# Breakout.net
KiCad netlist of a schematic drawn in EAGLE
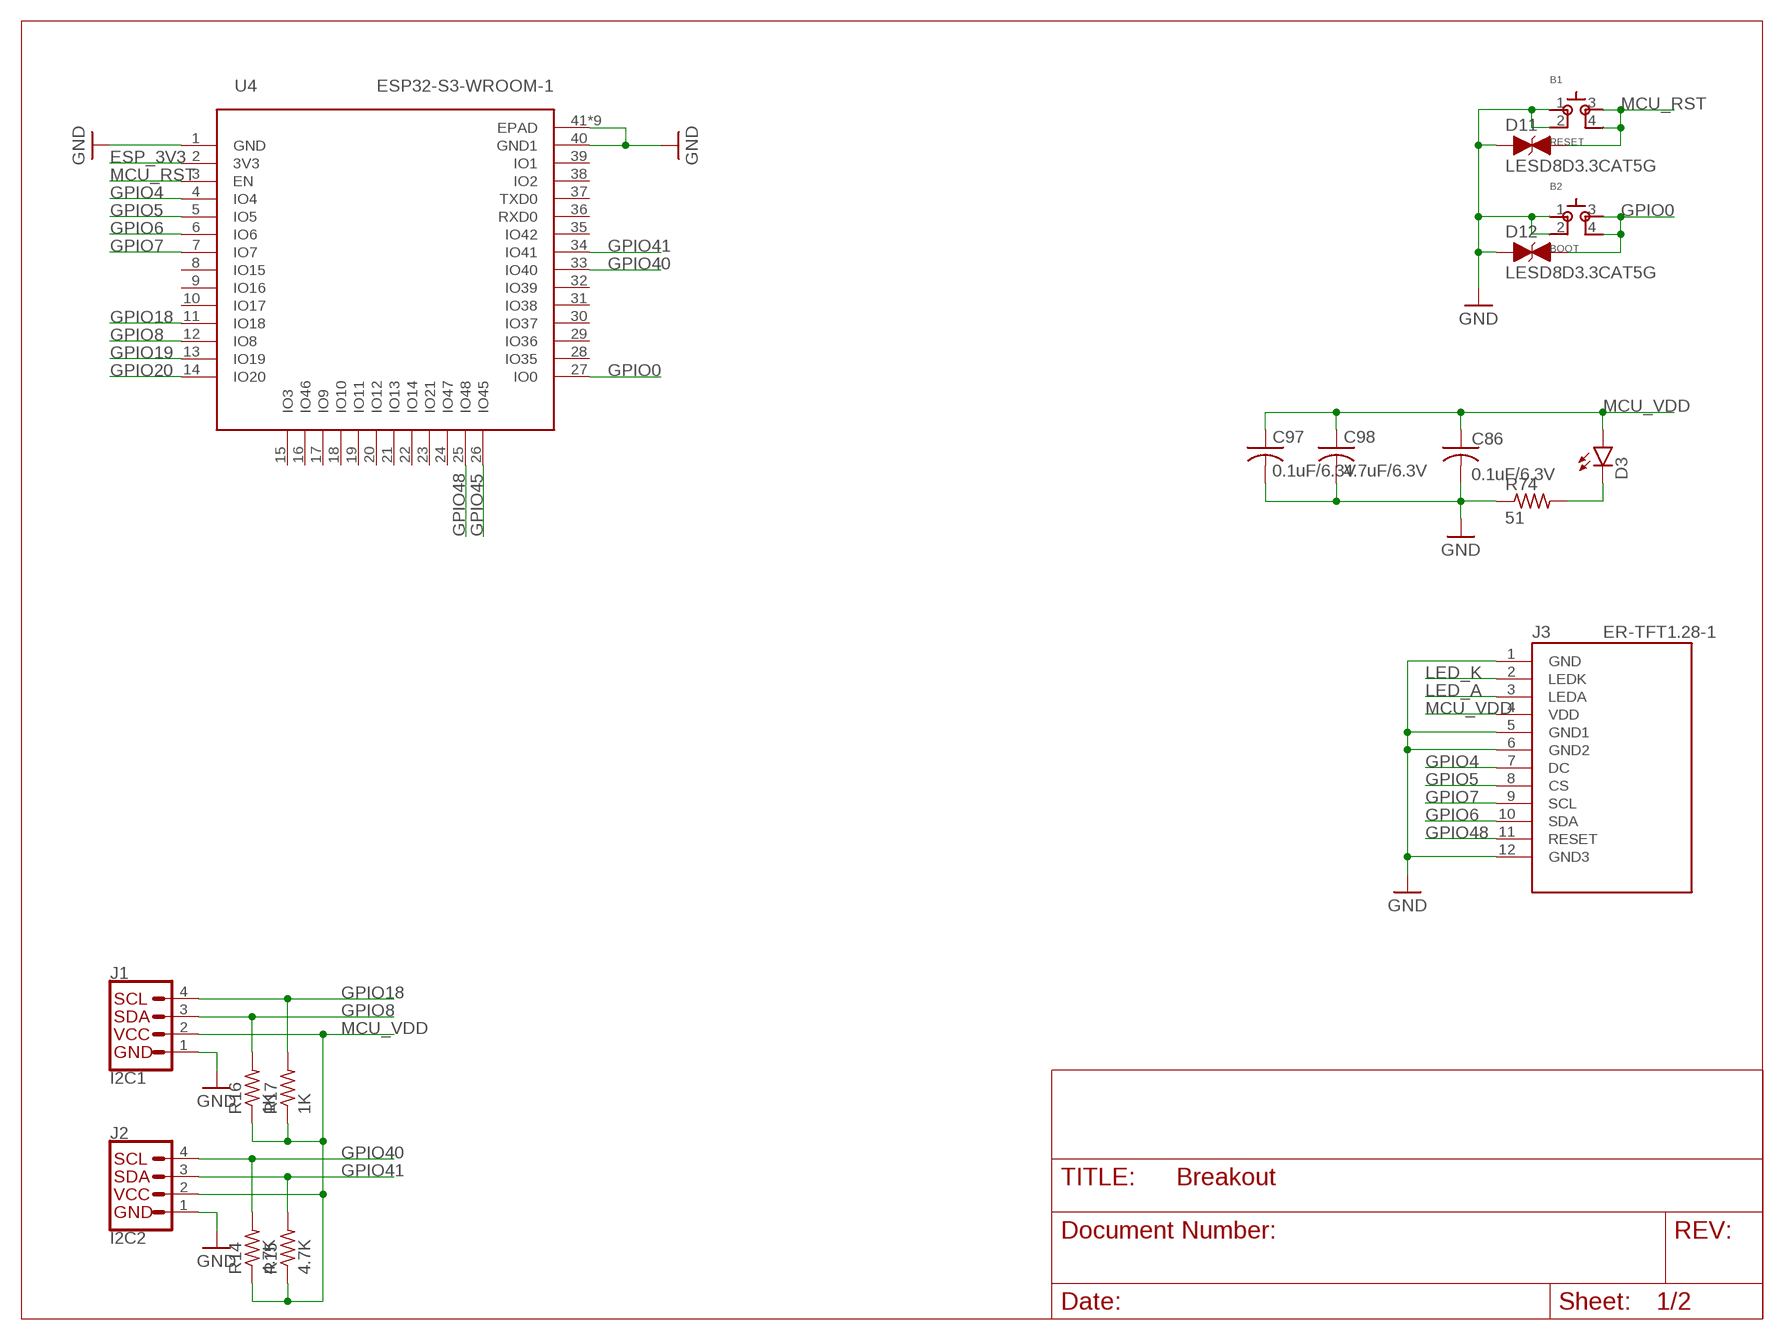
[diagram p0: schematic, sheet 1]
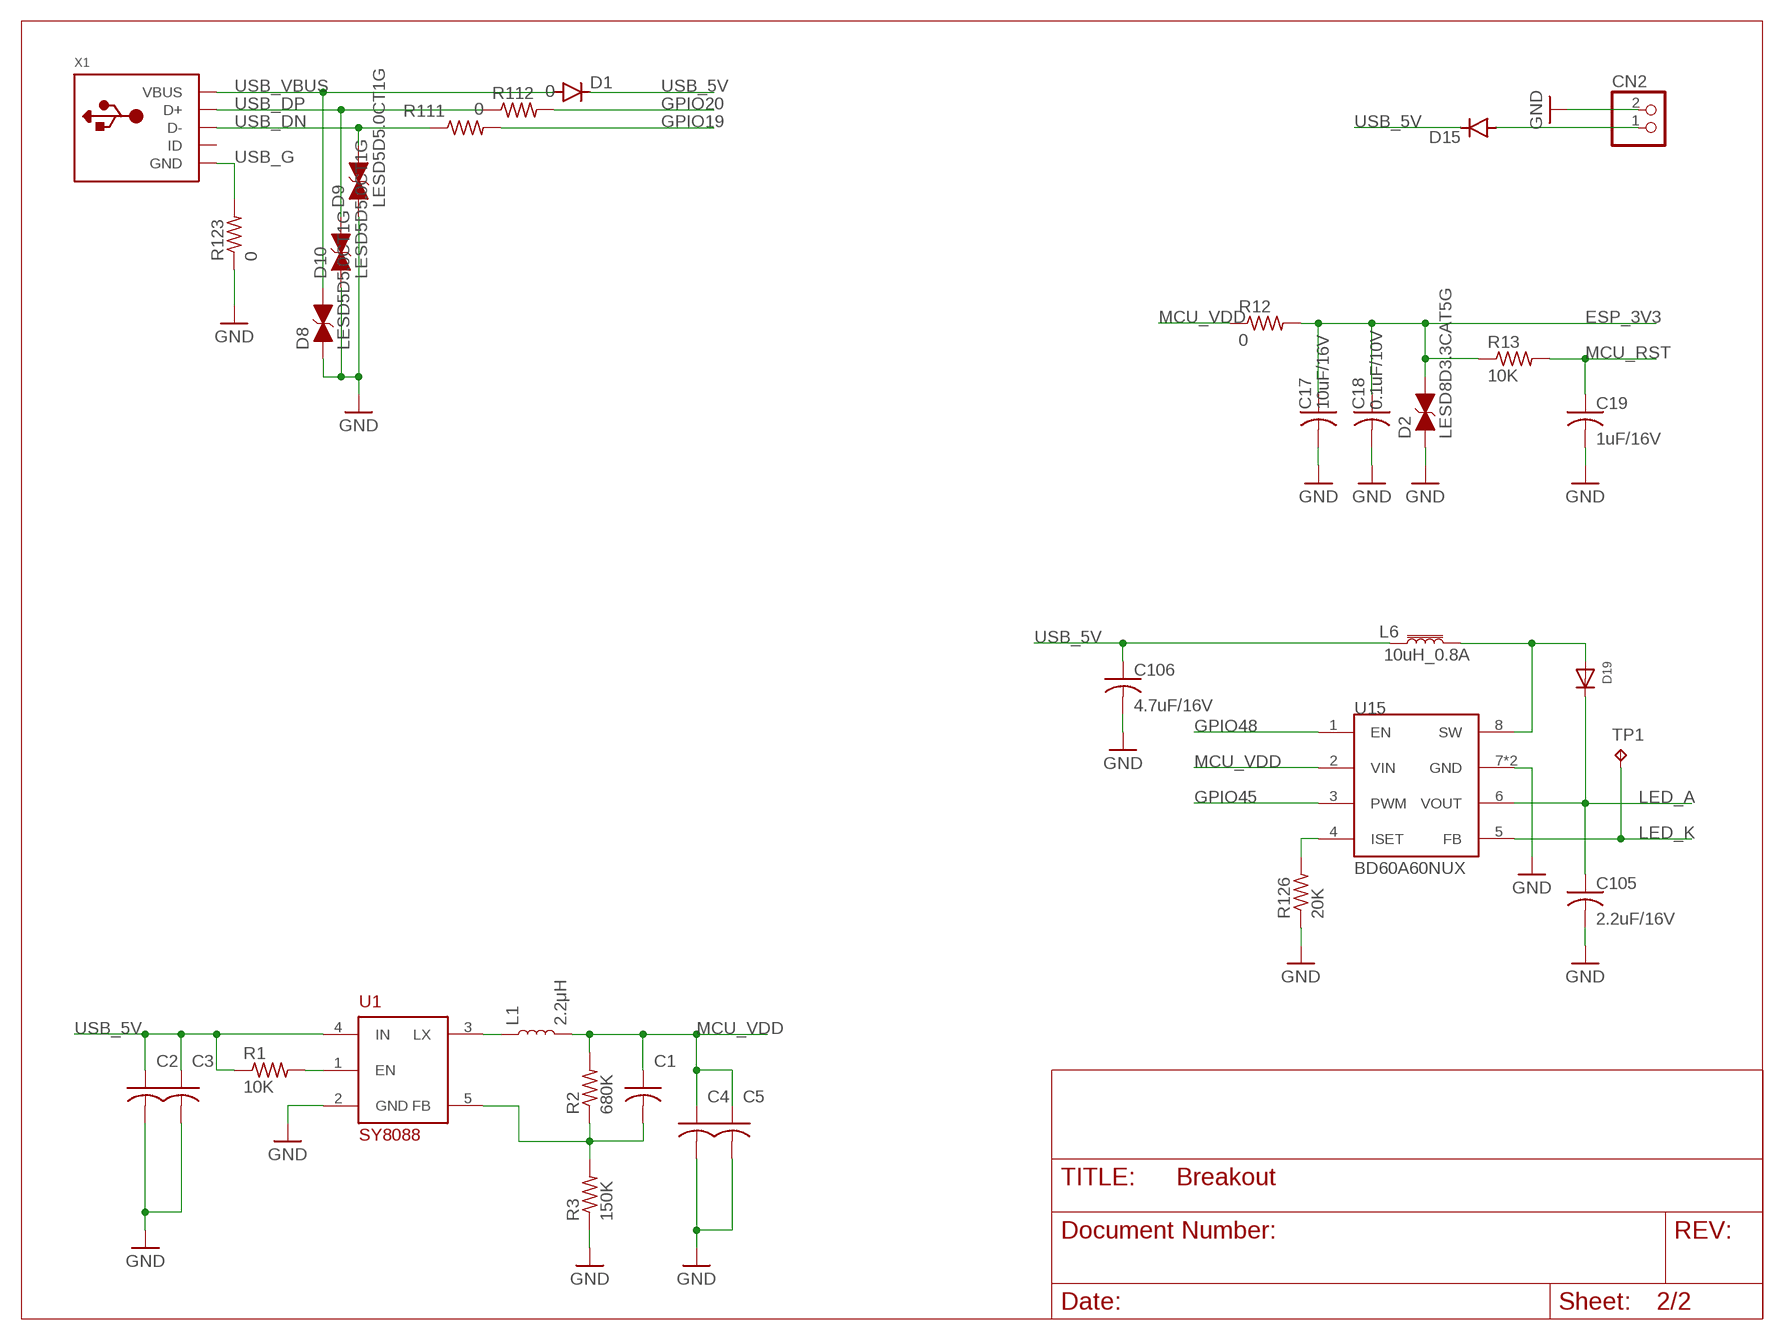
[diagram p1: schematic, sheet 2]

(export (version "E")
  (design (tool "Eeschema 10.0.6"))
  (components
    (comp (ref "B1")
      (value "RESET")
      (footprint "eagle-import:SKSCLDE010")
      (libsource (lib "eagle-import") (part "SKSCLDE010"))
    )
    (comp (ref "B2")
      (value "BOOT")
      (footprint "eagle-import:SKSCLDE010")
      (libsource (lib "eagle-import") (part "SKSCLDE010"))
    )
    (comp (ref "C86")
      (value "0.1uF/6.3V")
      (footprint "eagle-import:C0402")
      (libsource (lib "eagle-import") (part "C-USC0402"))
    )
    (comp (ref "C97")
      (value "0.1uF/6.3V")
      (footprint "eagle-import:C0402")
      (libsource (lib "eagle-import") (part "C-USC0402"))
    )
    (comp (ref "C98")
      (value "4.7uF/6.3V")
      (footprint "eagle-import:C0402")
      (libsource (lib "eagle-import") (part "C-USC0402"))
    )
    (comp (ref "D3")
      (value "LEDCHIPLED_1206")
      (footprint "eagle-import:CHIPLED_1206")
      (libsource (lib "eagle-import") (part "LEDCHIPLED_1206"))
    )
    (comp (ref "D11")
      (value "LESD8D3.3CAT5G")
      (footprint "eagle-import:SOD882")
      (libsource (lib "eagle-import") (part "LESD8D3.3CAT5G"))
    )
    (comp (ref "D12")
      (value "LESD8D3.3CAT5G")
      (footprint "eagle-import:SOD882")
      (libsource (lib "eagle-import") (part "LESD8D3.3CAT5G"))
    )
    (comp (ref "J1")
      (value "I2C1")
      (footprint "eagle-import:JST04_1MM_VERT")
      (libsource (lib "eagle-import") (part "QWIIC_CONNECTOR"))
    )
    (comp (ref "J2")
      (value "I2C2")
      (footprint "eagle-import:JST04_1MM_VERT")
      (libsource (lib "eagle-import") (part "QWIIC_CONNECTOR"))
    )
    (comp (ref "J3")
      (value "ER-TFT1.28-1")
      (footprint "eagle-import:12P-FPC")
      (libsource (lib "eagle-import") (part "ER-TFT1.28-1"))
    )
    (comp (ref "R14")
      (value "4.7K")
      (footprint "eagle-import:R0201")
      (libsource (lib "eagle-import") (part "R-US_R0201"))
    )
    (comp (ref "R15")
      (value "4.7K")
      (footprint "eagle-import:R0201")
      (libsource (lib "eagle-import") (part "R-US_R0201"))
    )
    (comp (ref "R16")
      (value "1K")
      (footprint "eagle-import:R0201")
      (libsource (lib "eagle-import") (part "R-US_R0201"))
    )
    (comp (ref "R17")
      (value "1K")
      (footprint "eagle-import:R0201")
      (libsource (lib "eagle-import") (part "R-US_R0201"))
    )
    (comp (ref "R74")
      (value "51")
      (footprint "eagle-import:R0201")
      (libsource (lib "eagle-import") (part "R-US_R0201"))
    )
    (comp (ref "U4")
      (value "ESP32-S3-WROOM-1")
      (footprint "eagle-import:QFN60_ESP32-S3-WROOM-1_EXP")
      (libsource (lib "eagle-import") (part "ESP32-S3-WROOM-1"))
    )
    (comp (ref "C1")
      (value "22pF/50V")
      (footprint "eagle-import:C0402")
      (libsource (lib "eagle-import") (part "C-USC0402"))
    )
    (comp (ref "C2")
      (value "10uF/16V")
      (footprint "eagle-import:C0603")
      (libsource (lib "eagle-import") (part "C-USC0603"))
    )
    (comp (ref "C3")
      (value "0.1uF/10V")
      (footprint "eagle-import:C0603")
      (libsource (lib "eagle-import") (part "C-USC0603"))
    )
    (comp (ref "C4")
      (value "0.1uF/10V")
      (footprint "eagle-import:C0402")
      (libsource (lib "eagle-import") (part "C-USC0402"))
    )
    (comp (ref "C5")
      (value "10uF/16V")
      (footprint "eagle-import:C0402")
      (libsource (lib "eagle-import") (part "C-USC0402"))
    )
    (comp (ref "C17")
      (value "10uF/16V")
      (footprint "eagle-import:C0603")
      (libsource (lib "eagle-import") (part "C-USC0603"))
    )
    (comp (ref "C18")
      (value "0.1uF/10V")
      (footprint "eagle-import:C0402")
      (libsource (lib "eagle-import") (part "C-USC0402"))
    )
    (comp (ref "C19")
      (value "1uF/16V")
      (footprint "eagle-import:C0402")
      (libsource (lib "eagle-import") (part "C-USC0402"))
    )
    (comp (ref "C105")
      (value "2.2uF/16V")
      (footprint "eagle-import:C0603")
      (libsource (lib "eagle-import") (part "C-USC0603"))
    )
    (comp (ref "C106")
      (value "4.7uF/16V")
      (footprint "eagle-import:C0603")
      (libsource (lib "eagle-import") (part "C-USC0603"))
    )
    (comp (ref "CN2")
      (value "JST_2PIN-SMT")
      (footprint "eagle-import:JST-PH-2-SMT")
      (libsource (lib "eagle-import") (part "JST_2PIN-SMT"))
    )
    (comp (ref "D1")
      (value "DIODE-SOD123")
      (footprint "eagle-import:SOD123")
      (libsource (lib "eagle-import") (part "DIODE-SOD123"))
    )
    (comp (ref "D2")
      (value "LESD8D3.3CAT5G")
      (footprint "eagle-import:SOD882")
      (libsource (lib "eagle-import") (part "LESD8D3.3CAT5G"))
    )
    (comp (ref "D8")
      (value "LESD5D5.0CT1G")
      (footprint "eagle-import:SOD523")
      (libsource (lib "eagle-import") (part "LESD5D5.0CT1G"))
    )
    (comp (ref "D9")
      (value "LESD5D5.0CT1G")
      (footprint "eagle-import:SOD523")
      (libsource (lib "eagle-import") (part "LESD5D5.0CT1G"))
    )
    (comp (ref "D10")
      (value "LESD5D5.0CT1G")
      (footprint "eagle-import:SOD523")
      (libsource (lib "eagle-import") (part "LESD5D5.0CT1G"))
    )
    (comp (ref "D15")
      (value "DIODE-SOD123")
      (footprint "eagle-import:SOD123")
      (libsource (lib "eagle-import") (part "DIODE-SOD123"))
    )
    (comp (ref "D19")
      (value "DIODESOD-523")
      (footprint "eagle-import:SOD-523")
      (libsource (lib "eagle-import") (part "DIODESOD-523"))
    )
    (comp (ref "L1")
      (value "2.2μH")
      (footprint "eagle-import:INDUCTOR_4X4MM")
      (libsource (lib "eagle-import") (part "2.2μH-4X4-2.2μH-3A-45MOHM"))
    )
    (comp (ref "L6")
      (value "10uH_0.8A")
      (footprint "eagle-import:L3012S")
      (libsource (lib "eagle-import") (part "SRN3010TA"))
    )
    (comp (ref "R1")
      (value "10K")
      (footprint "eagle-import:R0402")
      (libsource (lib "eagle-import") (part "R-US_R0402"))
    )
    (comp (ref "R2")
      (value "680K")
      (footprint "eagle-import:R0402")
      (libsource (lib "eagle-import") (part "R-US_R0402"))
    )
    (comp (ref "R3")
      (value "150K")
      (footprint "eagle-import:R0402")
      (libsource (lib "eagle-import") (part "R-US_R0402"))
    )
    (comp (ref "R12")
      (value "0")
      (footprint "eagle-import:R0603")
      (libsource (lib "eagle-import") (part "R-US_R0603"))
    )
    (comp (ref "R13")
      (value "10K")
      (footprint "eagle-import:R0402")
      (libsource (lib "eagle-import") (part "R-US_R0402"))
    )
    (comp (ref "R111")
      (value "0")
      (footprint "eagle-import:R0201")
      (libsource (lib "eagle-import") (part "R-US_R0201"))
    )
    (comp (ref "R112")
      (value "0")
      (footprint "eagle-import:R0201")
      (libsource (lib "eagle-import") (part "R-US_R0201"))
    )
    (comp (ref "R123")
      (value "0")
      (footprint "eagle-import:R0603")
      (libsource (lib "eagle-import") (part "R-US_R0603"))
    )
    (comp (ref "R126")
      (value "20K")
      (footprint "eagle-import:R0402")
      (libsource (lib "eagle-import") (part "R-US_R0402"))
    )
    (comp (ref "TP1")
      (value "TPTP06R")
      (footprint "eagle-import:TP06R")
      (libsource (lib "eagle-import") (part "TPTP06R"))
    )
    (comp (ref "U1")
      (value "SY8088")
      (footprint "eagle-import:SOT23-5")
      (libsource (lib "eagle-import") (part "SY8088"))
    )
    (comp (ref "U15")
      (value "BD60A60NUX")
      (footprint "eagle-import:VSON008X2030")
      (libsource (lib "eagle-import") (part "BD60A60NUX"))
    )
    (comp (ref "X1")
      (value "MICROBUILDER_USBMICRO_20329")
      (footprint "eagle-import:MICROBUILDER_4UCONN_20329")
      (libsource (lib "eagle-import") (part "MICROBUILDER_USBMICRO_20329"))
    )
  )
  (nets
    (net (code "1") (name "ESP_3V3") (class "Default")
      (node (ref "C17") (pin "1") (pinfunction "1_1") (pintype "passive"))
      (node (ref "C18") (pin "1") (pinfunction "1_1") (pintype "passive"))
      (node (ref "D2") (pin "C") (pinfunction "C_C") (pintype "passive"))
      (node (ref "R12") (pin "2") (pinfunction "2_2") (pintype "passive"))
      (node (ref "R13") (pin "1") (pinfunction "1_1") (pintype "passive"))
      (node (ref "U4") (pin "2") (pinfunction "3V3_2") (pintype "power_in"))
    )
    (net (code "2") (name "GND") (class "Default")
      (node (ref "B1") (pin "1") (pinfunction "1_1") (pintype "bidirectional"))
      (node (ref "B1") (pin "2") (pinfunction "2_2") (pintype "bidirectional"))
      (node (ref "B2") (pin "1") (pinfunction "1_1") (pintype "bidirectional"))
      (node (ref "B2") (pin "2") (pinfunction "2_2") (pintype "bidirectional"))
      (node (ref "C105") (pin "2") (pinfunction "2_2") (pintype "passive"))
      (node (ref "C106") (pin "2") (pinfunction "2_2") (pintype "passive"))
      (node (ref "C17") (pin "2") (pinfunction "2_2") (pintype "passive"))
      (node (ref "C18") (pin "2") (pinfunction "2_2") (pintype "passive"))
      (node (ref "C19") (pin "2") (pinfunction "2_2") (pintype "passive"))
      (node (ref "C2") (pin "2") (pinfunction "2_2") (pintype "passive"))
      (node (ref "C3") (pin "2") (pinfunction "2_2") (pintype "passive"))
      (node (ref "C4") (pin "2") (pinfunction "2_2") (pintype "passive"))
      (node (ref "C5") (pin "2") (pinfunction "2_2") (pintype "passive"))
      (node (ref "C86") (pin "2") (pinfunction "2_2") (pintype "passive"))
      (node (ref "C97") (pin "2") (pinfunction "2_2") (pintype "passive"))
      (node (ref "C98") (pin "2") (pinfunction "2_2") (pintype "passive"))
      (node (ref "CN2") (pin "2") (pinfunction "1_2") (pintype "passive"))
      (node (ref "D10") (pin "A") (pinfunction "A_A") (pintype "passive"))
      (node (ref "D11") (pin "A") (pinfunction "A_A") (pintype "passive"))
      (node (ref "D12") (pin "A") (pinfunction "A_A") (pintype "passive"))
      (node (ref "D2") (pin "A") (pinfunction "A_A") (pintype "passive"))
      (node (ref "D8") (pin "A") (pinfunction "A_A") (pintype "passive"))
      (node (ref "D9") (pin "A") (pinfunction "A_A") (pintype "passive"))
      (node (ref "J1") (pin "1") (pinfunction "1_1") (pintype "power_in"))
      (node (ref "J2") (pin "1") (pinfunction "1_1") (pintype "power_in"))
      (node (ref "J3") (pin "1") (pinfunction "GND_1") (pintype "bidirectional"))
      (node (ref "J3") (pin "12") (pinfunction "GND3_12") (pintype "bidirectional"))
      (node (ref "J3") (pin "5") (pinfunction "GND1_5") (pintype "bidirectional"))
      (node (ref "J3") (pin "6") (pinfunction "GND2_6") (pintype "bidirectional"))
      (node (ref "R123") (pin "1") (pinfunction "1_1") (pintype "passive"))
      (node (ref "R126") (pin "1") (pinfunction "1_1") (pintype "passive"))
      (node (ref "R3") (pin "1") (pinfunction "1_1") (pintype "passive"))
      (node (ref "R74") (pin "1") (pinfunction "1_1") (pintype "passive"))
      (node (ref "U1") (pin "2") (pinfunction "GND_2") (pintype "bidirectional"))
      (node (ref "U15") (pin "7") (pinfunction "GND_7") (pintype "bidirectional"))
      (node (ref "U15") (pin "PAD") (pinfunction "GND_PAD") (pintype "bidirectional"))
      (node (ref "U4") (pin "1") (pinfunction "GND_1") (pintype "bidirectional"))
      (node (ref "U4") (pin "40") (pinfunction "GND1_40") (pintype "bidirectional"))
      (node (ref "U4") (pin "41") (pinfunction "EPAD_41") (pintype "bidirectional"))
      (node (ref "U4") (pin "42") (pinfunction "EPAD_42") (pintype "bidirectional"))
      (node (ref "U4") (pin "43") (pinfunction "EPAD_43") (pintype "bidirectional"))
      (node (ref "U4") (pin "44") (pinfunction "EPAD_44") (pintype "bidirectional"))
      (node (ref "U4") (pin "45") (pinfunction "EPAD_45") (pintype "bidirectional"))
      (node (ref "U4") (pin "46") (pinfunction "EPAD_46") (pintype "bidirectional"))
      (node (ref "U4") (pin "47") (pinfunction "EPAD_47") (pintype "bidirectional"))
      (node (ref "U4") (pin "48") (pinfunction "EPAD_48") (pintype "bidirectional"))
      (node (ref "U4") (pin "49") (pinfunction "EPAD_49") (pintype "bidirectional"))
    )
    (net (code "3") (name "GPIO0") (class "Default")
      (node (ref "B2") (pin "3") (pinfunction "4_3") (pintype "bidirectional"))
      (node (ref "B2") (pin "4") (pinfunction "3_4") (pintype "bidirectional"))
      (node (ref "D12") (pin "C") (pinfunction "C_C") (pintype "passive"))
      (node (ref "U4") (pin "27") (pinfunction "IO0_27") (pintype "bidirectional"))
    )
    (net (code "4") (name "GPIO4") (class "Default")
      (node (ref "J3") (pin "7") (pinfunction "DC_7") (pintype "bidirectional"))
      (node (ref "U4") (pin "4") (pinfunction "IO4_4") (pintype "bidirectional"))
    )
    (net (code "5") (name "GPIO5") (class "Default")
      (node (ref "J3") (pin "8") (pinfunction "CS_8") (pintype "bidirectional"))
      (node (ref "U4") (pin "5") (pinfunction "IO5_5") (pintype "bidirectional"))
    )
    (net (code "6") (name "GPIO6") (class "Default")
      (node (ref "J3") (pin "10") (pinfunction "SDA_10") (pintype "bidirectional"))
      (node (ref "U4") (pin "6") (pinfunction "IO6_6") (pintype "bidirectional"))
    )
    (net (code "7") (name "GPIO7") (class "Default")
      (node (ref "J3") (pin "9") (pinfunction "SCL_9") (pintype "bidirectional"))
      (node (ref "U4") (pin "7") (pinfunction "IO7_7") (pintype "bidirectional"))
    )
    (net (code "8") (name "GPIO8") (class "Default")
      (node (ref "J1") (pin "3") (pinfunction "3_3") (pintype "passive"))
      (node (ref "R16") (pin "2") (pinfunction "2_2") (pintype "passive"))
      (node (ref "U4") (pin "12") (pinfunction "IO8_12") (pintype "bidirectional"))
    )
    (net (code "9") (name "GPIO18") (class "Default")
      (node (ref "J1") (pin "4") (pinfunction "4_4") (pintype "passive"))
      (node (ref "R17") (pin "2") (pinfunction "2_2") (pintype "passive"))
      (node (ref "U4") (pin "11") (pinfunction "IO18_11") (pintype "bidirectional"))
    )
    (net (code "10") (name "GPIO19") (class "Default")
      (node (ref "R111") (pin "2") (pinfunction "2_2") (pintype "passive"))
      (node (ref "U4") (pin "13") (pinfunction "IO19_13") (pintype "bidirectional"))
    )
    (net (code "11") (name "GPIO20") (class "Default")
      (node (ref "R112") (pin "2") (pinfunction "2_2") (pintype "passive"))
      (node (ref "U4") (pin "14") (pinfunction "IO20_14") (pintype "bidirectional"))
    )
    (net (code "12") (name "GPIO40") (class "Default")
      (node (ref "J2") (pin "4") (pinfunction "4_4") (pintype "passive"))
      (node (ref "R14") (pin "2") (pinfunction "2_2") (pintype "passive"))
      (node (ref "U4") (pin "33") (pinfunction "IO40_33") (pintype "bidirectional"))
    )
    (net (code "13") (name "GPIO41") (class "Default")
      (node (ref "J2") (pin "3") (pinfunction "3_3") (pintype "passive"))
      (node (ref "R15") (pin "2") (pinfunction "2_2") (pintype "passive"))
      (node (ref "U4") (pin "34") (pinfunction "IO41_34") (pintype "bidirectional"))
    )
    (net (code "14") (name "GPIO45") (class "Default")
      (node (ref "U15") (pin "3") (pinfunction "PWM_3") (pintype "bidirectional"))
      (node (ref "U4") (pin "26") (pinfunction "IO45_26") (pintype "bidirectional"))
    )
    (net (code "15") (name "GPIO48") (class "Default")
      (node (ref "J3") (pin "11") (pinfunction "RESET_11") (pintype "bidirectional"))
      (node (ref "U15") (pin "1") (pinfunction "EN_1") (pintype "bidirectional"))
      (node (ref "U4") (pin "25") (pinfunction "IO48_25") (pintype "bidirectional"))
    )
    (net (code "16") (name "LED_A") (class "Default")
      (node (ref "C105") (pin "1") (pinfunction "1_1") (pintype "passive"))
      (node (ref "D19") (pin "K") (pinfunction "C_K") (pintype "passive"))
      (node (ref "J3") (pin "3") (pinfunction "LEDA_3") (pintype "bidirectional"))
      (node (ref "U15") (pin "6") (pinfunction "VOUT_6") (pintype "bidirectional"))
    )
    (net (code "17") (name "LED_K") (class "Default")
      (node (ref "J3") (pin "2") (pinfunction "LEDK_2") (pintype "bidirectional"))
      (node (ref "TP1") (pin "TP") (pinfunction "TP_TP") (pintype "input"))
      (node (ref "U15") (pin "5") (pinfunction "FB_5") (pintype "bidirectional"))
    )
    (net (code "18") (name "MCU_RST") (class "Default")
      (node (ref "B1") (pin "3") (pinfunction "4_3") (pintype "bidirectional"))
      (node (ref "B1") (pin "4") (pinfunction "3_4") (pintype "bidirectional"))
      (node (ref "C19") (pin "1") (pinfunction "1_1") (pintype "passive"))
      (node (ref "D11") (pin "C") (pinfunction "C_C") (pintype "passive"))
      (node (ref "R13") (pin "2") (pinfunction "2_2") (pintype "passive"))
      (node (ref "U4") (pin "3") (pinfunction "EN_3") (pintype "bidirectional"))
    )
    (net (code "19") (name "MCU_VDD") (class "Default")
      (node (ref "C1") (pin "1") (pinfunction "1_1") (pintype "passive"))
      (node (ref "C4") (pin "1") (pinfunction "1_1") (pintype "passive"))
      (node (ref "C5") (pin "1") (pinfunction "1_1") (pintype "passive"))
      (node (ref "C86") (pin "1") (pinfunction "1_1") (pintype "passive"))
      (node (ref "C97") (pin "1") (pinfunction "1_1") (pintype "passive"))
      (node (ref "C98") (pin "1") (pinfunction "1_1") (pintype "passive"))
      (node (ref "D3") (pin "A") (pinfunction "A_A") (pintype "passive"))
      (node (ref "J1") (pin "2") (pinfunction "2_2") (pintype "power_in"))
      (node (ref "J2") (pin "2") (pinfunction "2_2") (pintype "power_in"))
      (node (ref "J3") (pin "4") (pinfunction "VDD_4") (pintype "bidirectional"))
      (node (ref "L1") (pin "P$2") (pinfunction "2_P$2") (pintype "passive"))
      (node (ref "R12") (pin "1") (pinfunction "1_1") (pintype "passive"))
      (node (ref "R14") (pin "1") (pinfunction "1_1") (pintype "passive"))
      (node (ref "R15") (pin "1") (pinfunction "1_1") (pintype "passive"))
      (node (ref "R16") (pin "1") (pinfunction "1_1") (pintype "passive"))
      (node (ref "R17") (pin "1") (pinfunction "1_1") (pintype "passive"))
      (node (ref "R2") (pin "2") (pinfunction "2_2") (pintype "passive"))
      (node (ref "U15") (pin "2") (pinfunction "VIN_2") (pintype "bidirectional"))
    )
    (net (code "20") (name "Net-(CN2-2)") (class "Default")
      (node (ref "CN2") (pin "1") (pinfunction "2_1") (pintype "passive"))
      (node (ref "D15") (pin "A") (pinfunction "A_A") (pintype "passive"))
    )
    (net (code "21") (name "Net-(D3-PadC)") (class "Default")
      (node (ref "D3") (pin "C") (pinfunction "C_C") (pintype "passive"))
      (node (ref "R74") (pin "2") (pinfunction "2_2") (pintype "passive"))
    )
    (net (code "22") (name "Net-(L1-1)") (class "Default")
      (node (ref "L1") (pin "P$1") (pinfunction "1_P$1") (pintype "passive"))
      (node (ref "U1") (pin "3") (pinfunction "LX_3") (pintype "bidirectional"))
    )
    (net (code "23") (name "Net-(L6-2)") (class "Default")
      (node (ref "D19") (pin "A") (pinfunction "A_A") (pintype "passive"))
      (node (ref "L6") (pin "P$2") (pinfunction "2_P$2") (pintype "passive"))
      (node (ref "U15") (pin "8") (pinfunction "SW_8") (pintype "bidirectional"))
    )
    (net (code "24") (name "Net-(U1-EN)") (class "Default")
      (node (ref "R1") (pin "2") (pinfunction "2_2") (pintype "passive"))
      (node (ref "U1") (pin "1") (pinfunction "EN_1") (pintype "bidirectional"))
    )
    (net (code "25") (name "Net-(U1-FB)") (class "Default")
      (node (ref "C1") (pin "2") (pinfunction "2_2") (pintype "passive"))
      (node (ref "R2") (pin "1") (pinfunction "1_1") (pintype "passive"))
      (node (ref "R3") (pin "2") (pinfunction "2_2") (pintype "passive"))
      (node (ref "U1") (pin "5") (pinfunction "FB_5") (pintype "bidirectional"))
    )
    (net (code "26") (name "Net-(U15-ISET)") (class "Default")
      (node (ref "R126") (pin "2") (pinfunction "2_2") (pintype "passive"))
      (node (ref "U15") (pin "4") (pinfunction "ISET_4") (pintype "bidirectional"))
    )
    (net (code "27") (name "USB_5V") (class "Default")
      (node (ref "C106") (pin "1") (pinfunction "1_1") (pintype "passive"))
      (node (ref "C2") (pin "1") (pinfunction "1_1") (pintype "passive"))
      (node (ref "C3") (pin "1") (pinfunction "1_1") (pintype "passive"))
      (node (ref "D1") (pin "C") (pinfunction "C_C") (pintype "passive"))
      (node (ref "D15") (pin "C") (pinfunction "C_C") (pintype "passive"))
      (node (ref "L6") (pin "P$1") (pinfunction "1_P$1") (pintype "passive"))
      (node (ref "R1") (pin "1") (pinfunction "1_1") (pintype "passive"))
      (node (ref "U1") (pin "4") (pinfunction "IN_4") (pintype "bidirectional"))
    )
    (net (code "28") (name "USB_DN") (class "Default")
      (node (ref "D9") (pin "C") (pinfunction "C_C") (pintype "passive"))
      (node (ref "R111") (pin "1") (pinfunction "1_1") (pintype "passive"))
      (node (ref "X1") (pin "D-") (pinfunction "D-_D-") (pintype "bidirectional"))
    )
    (net (code "29") (name "USB_DP") (class "Default")
      (node (ref "D10") (pin "C") (pinfunction "C_C") (pintype "passive"))
      (node (ref "R112") (pin "1") (pinfunction "1_1") (pintype "passive"))
      (node (ref "X1") (pin "D+") (pinfunction "D+_D+") (pintype "bidirectional"))
    )
    (net (code "30") (name "USB_G") (class "Default")
      (node (ref "R123") (pin "2") (pinfunction "2_2") (pintype "passive"))
      (node (ref "X1") (pin "BASE@1") (pinfunction "GND_BASE@1") (pintype "power_in"))
      (node (ref "X1") (pin "BASE@2") (pinfunction "GND_BASE@2") (pintype "power_in"))
      (node (ref "X1") (pin "GND") (pinfunction "GND_GND") (pintype "power_in"))
      (node (ref "X1") (pin "SPRT@1") (pinfunction "GND_SPRT@1") (pintype "power_in"))
      (node (ref "X1") (pin "SPRT@2") (pinfunction "GND_SPRT@2") (pintype "power_in"))
      (node (ref "X1") (pin "SPRT@3") (pinfunction "GND_SPRT@3") (pintype "power_in"))
      (node (ref "X1") (pin "SPRT@4") (pinfunction "GND_SPRT@4") (pintype "power_in"))
    )
    (net (code "31") (name "USB_VBUS") (class "Default")
      (node (ref "D1") (pin "A") (pinfunction "A_A") (pintype "passive"))
      (node (ref "D8") (pin "C") (pinfunction "C_C") (pintype "passive"))
      (node (ref "X1") (pin "VBUS") (pinfunction "VBUS_VBUS") (pintype "power_in"))
    )
    (net (code "32") (name "unconnected-(U4-IO1-Pad39)") (class "Default")
      (node (ref "U4") (pin "39") (pinfunction "IO1_39") (pintype "bidirectional"))
    )
    (net (code "33") (name "unconnected-(U4-IO2-Pad38)") (class "Default")
      (node (ref "U4") (pin "38") (pinfunction "IO2_38") (pintype "bidirectional"))
    )
    (net (code "34") (name "unconnected-(U4-IO3-Pad15)") (class "Default")
      (node (ref "U4") (pin "15") (pinfunction "IO3_15") (pintype "bidirectional"))
    )
    (net (code "35") (name "unconnected-(U4-IO9-Pad17)") (class "Default")
      (node (ref "U4") (pin "17") (pinfunction "IO9_17") (pintype "bidirectional"))
    )
    (net (code "36") (name "unconnected-(U4-IO10-Pad18)") (class "Default")
      (node (ref "U4") (pin "18") (pinfunction "IO10_18") (pintype "bidirectional"))
    )
    (net (code "37") (name "unconnected-(U4-IO11-Pad19)") (class "Default")
      (node (ref "U4") (pin "19") (pinfunction "IO11_19") (pintype "bidirectional"))
    )
    (net (code "38") (name "unconnected-(U4-IO12-Pad20)") (class "Default")
      (node (ref "U4") (pin "20") (pinfunction "IO12_20") (pintype "bidirectional"))
    )
    (net (code "39") (name "unconnected-(U4-IO13-Pad21)") (class "Default")
      (node (ref "U4") (pin "21") (pinfunction "IO13_21") (pintype "bidirectional"))
    )
    (net (code "40") (name "unconnected-(U4-IO14-Pad22)") (class "Default")
      (node (ref "U4") (pin "22") (pinfunction "IO14_22") (pintype "bidirectional"))
    )
    (net (code "41") (name "unconnected-(U4-IO15-Pad8)") (class "Default")
      (node (ref "U4") (pin "8") (pinfunction "IO15_8") (pintype "bidirectional"))
    )
    (net (code "42") (name "unconnected-(U4-IO16-Pad9)") (class "Default")
      (node (ref "U4") (pin "9") (pinfunction "IO16_9") (pintype "bidirectional"))
    )
    (net (code "43") (name "unconnected-(U4-IO17-Pad10)") (class "Default")
      (node (ref "U4") (pin "10") (pinfunction "IO17_10") (pintype "bidirectional"))
    )
    (net (code "44") (name "unconnected-(U4-IO21-Pad23)") (class "Default")
      (node (ref "U4") (pin "23") (pinfunction "IO21_23") (pintype "bidirectional"))
    )
    (net (code "45") (name "unconnected-(U4-IO35-Pad28)") (class "Default")
      (node (ref "U4") (pin "28") (pinfunction "IO35_28") (pintype "bidirectional"))
    )
    (net (code "46") (name "unconnected-(U4-IO36-Pad29)") (class "Default")
      (node (ref "U4") (pin "29") (pinfunction "IO36_29") (pintype "bidirectional"))
    )
    (net (code "47") (name "unconnected-(U4-IO37-Pad30)") (class "Default")
      (node (ref "U4") (pin "30") (pinfunction "IO37_30") (pintype "bidirectional"))
    )
    (net (code "48") (name "unconnected-(U4-IO38-Pad31)") (class "Default")
      (node (ref "U4") (pin "31") (pinfunction "IO38_31") (pintype "bidirectional"))
    )
    (net (code "49") (name "unconnected-(U4-IO39-Pad32)") (class "Default")
      (node (ref "U4") (pin "32") (pinfunction "IO39_32") (pintype "bidirectional"))
    )
    (net (code "50") (name "unconnected-(U4-IO42-Pad35)") (class "Default")
      (node (ref "U4") (pin "35") (pinfunction "IO42_35") (pintype "bidirectional"))
    )
    (net (code "51") (name "unconnected-(U4-IO46-Pad16)") (class "Default")
      (node (ref "U4") (pin "16") (pinfunction "IO46_16") (pintype "bidirectional"))
    )
    (net (code "52") (name "unconnected-(U4-IO47-Pad24)") (class "Default")
      (node (ref "U4") (pin "24") (pinfunction "IO47_24") (pintype "bidirectional"))
    )
    (net (code "53") (name "unconnected-(U4-RXD0-Pad36)") (class "Default")
      (node (ref "U4") (pin "36") (pinfunction "RXD0_36") (pintype "bidirectional"))
    )
    (net (code "54") (name "unconnected-(U4-TXD0-Pad37)") (class "Default")
      (node (ref "U4") (pin "37") (pinfunction "TXD0_37") (pintype "bidirectional"))
    )
    (net (code "55") (name "unconnected-(X1-PadID)") (class "Default")
      (node (ref "X1") (pin "ID") (pinfunction "ID_ID") (pintype "bidirectional"))
    )
  )
)
